# 16_-SP1_TYPEC_PWR_IN.net
KiCad netlist of a schematic drawn in Altium Designer
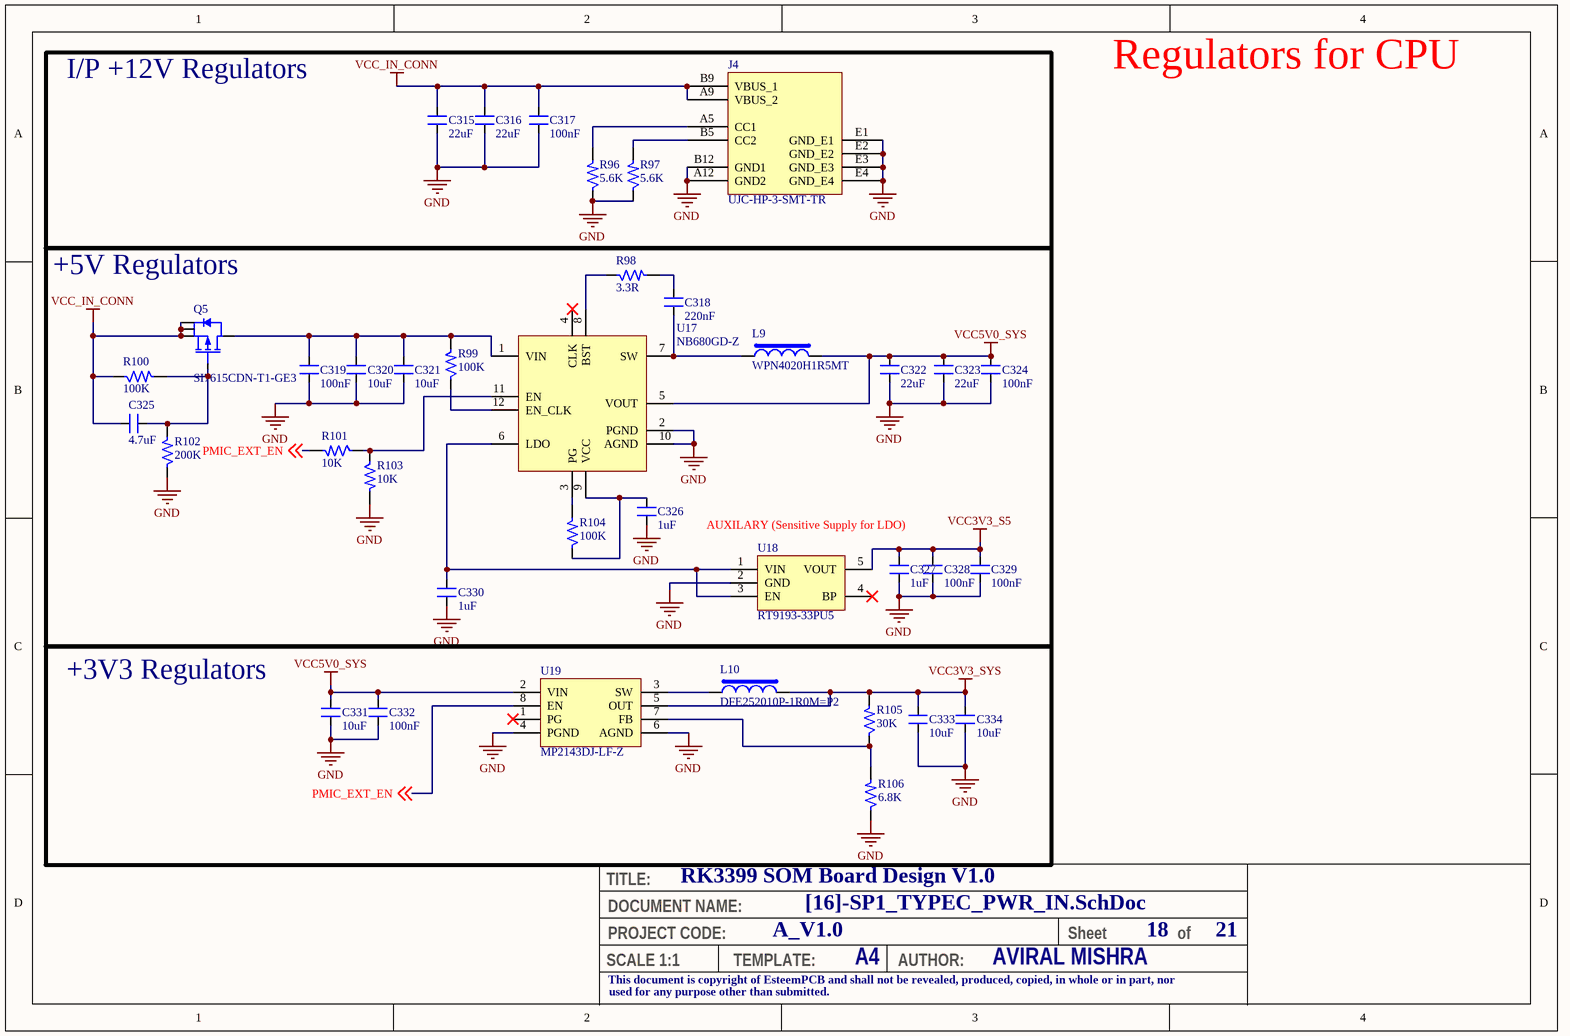
[diagram p0: [16]-SP1_TYPEC_PWR_IN.SchDoc]

(export (version "E")
  (design (tool "Eeschema 10.0.6"))
  (components
    (comp (ref "C315")
      (value "22uF")
      (footprint "CAP_0603")
      (description "22µF ±20% 10V Ceramic Capacitor X5R 0603 (1608 Metric)")
      (fields
        (field (name "MANUFACTURER") "Murata Electronics")
        (field (name "MANUFACTURER PART NUMBER") "GRM188R61A226ME15D")
      )
      (libsource (lib "RK3399 _Module_Schlib") (part "CAP_22uF-10V-20%-0603"))
    )
    (comp (ref "C316")
      (value "22uF")
      (footprint "CAP_0603")
      (description "22µF ±20% 10V Ceramic Capacitor X5R 0603 (1608 Metric)")
      (fields
        (field (name "MANUFACTURER") "Murata Electronics")
        (field (name "MANUFACTURER PART NUMBER") "GRM188R61A226ME15D")
      )
      (libsource (lib "RK3399 _Module_Schlib") (part "CAP_22uF-10V-20%-0603"))
    )
    (comp (ref "C317")
      (value "100nF")
      (footprint "CAP_0402")
      (description "0.1µF ±10% 25V Ceramic Capacitor X7R 0402 (1005 Metric)")
      (fields
        (field (name "MANUFACTURER") "Walsin Technology Corporation")
        (field (name "MANUFACTURER PART NUMBER") "0402B104K250CT")
      )
      (libsource (lib "RK3399 _Module_Schlib") (part "CAP_100nF-25V-10%-0402"))
    )
    (comp (ref "C318")
      (value "220nF")
      (footprint "CAP_0402")
      (description "0.22µF ±10% 10V Ceramic Capacitor X7R 0402 (1005 Metric)")
      (fields
        (field (name "MANUFACTURER") "Samsung Electro-Mechanics")
        (field (name "MANUFACTURER PART NUMBER") "CL05B224KP5NNNC")
      )
      (libsource (lib "RK3399 _Module_Schlib") (part "CAP_220nF-10V-10%-0402"))
    )
    (comp (ref "C319")
      (value "100nF")
      (footprint "CAP_0402")
      (description "0.1µF ±10% 25V Ceramic Capacitor X7R 0402 (1005 Metric)")
      (fields
        (field (name "MANUFACTURER") "Walsin Technology Corporation")
        (field (name "MANUFACTURER PART NUMBER") "0402B104K250CT")
      )
      (libsource (lib "RK3399 _Module_Schlib") (part "CAP_100nF-25V-10%-0402"))
    )
    (comp (ref "C320")
      (value "10uF")
      (footprint "CAP_0402")
      (description "10µF ±20% 10V Ceramic Capacitor X5R 0402 (1005 Metric)")
      (fields
        (field (name "MANUFACTURER PART NUMBER") "CL05A106MP5NUNC")
        (field (name "MANUFACTURER") "Samsung Electro-Mechanics")
      )
      (libsource (lib "RK3399 _Module_Schlib") (part "CAP_10uF-10V-20%-0402"))
    )
    (comp (ref "C321")
      (value "10uF")
      (footprint "CAP_0402")
      (description "10µF ±20% 10V Ceramic Capacitor X5R 0402 (1005 Metric)")
      (fields
        (field (name "MANUFACTURER PART NUMBER") "CL05A106MP5NUNC")
        (field (name "MANUFACTURER") "Samsung Electro-Mechanics")
      )
      (libsource (lib "RK3399 _Module_Schlib") (part "CAP_10uF-10V-20%-0402"))
    )
    (comp (ref "C322")
      (value "22uF")
      (footprint "CAP_0603")
      (description "22µF ±20% 10V Ceramic Capacitor X5R 0603 (1608 Metric)")
      (fields
        (field (name "MANUFACTURER") "Murata Electronics")
        (field (name "MANUFACTURER PART NUMBER") "GRM188R61A226ME15D")
      )
      (libsource (lib "RK3399 _Module_Schlib") (part "CAP_22uF-10V-20%-0603"))
    )
    (comp (ref "C323")
      (value "22uF")
      (footprint "CAP_0603")
      (description "22µF ±20% 10V Ceramic Capacitor X5R 0603 (1608 Metric)")
      (fields
        (field (name "MANUFACTURER") "Murata Electronics")
        (field (name "MANUFACTURER PART NUMBER") "GRM188R61A226ME15D")
      )
      (libsource (lib "RK3399 _Module_Schlib") (part "CAP_22uF-10V-20%-0603"))
    )
    (comp (ref "C324")
      (value "100nF")
      (footprint "CAP_0402")
      (description "0.1µF ±10% 25V Ceramic Capacitor X7R 0402 (1005 Metric)")
      (fields
        (field (name "MANUFACTURER") "Walsin Technology Corporation")
        (field (name "MANUFACTURER PART NUMBER") "0402B104K250CT")
      )
      (libsource (lib "RK3399 _Module_Schlib") (part "CAP_100nF-25V-10%-0402"))
    )
    (comp (ref "C325")
      (value "4.7uF")
      (footprint "CAP_0402")
      (description "4.7µF ±10% 10V Ceramic Capacitor X5R 0402 (1005 Metric)")
      (fields
        (field (name "MANUFACTURER") "Samsung Electro-Mechanics")
        (field (name "MANUFACTURER PART NUMBER") "CL05A475KP5NRNC")
      )
      (libsource (lib "RK3399 _Module_Schlib") (part "CAP_4.7uF-10V-10%-0402"))
    )
    (comp (ref "C326")
      (value "1uF")
      (footprint "CAP_0402")
      (description "1µF ±10% 16V Ceramic Capacitor X5R 0402 (1005 Metric)")
      (fields
        (field (name "MANUFACTURER") "Knowles Novacap")
        (field (name "MANUFACTURER PART NUMBER") "0402BW105K160YT")
      )
      (libsource (lib "RK3399 _Module_Schlib") (part "CAP_1uF-16V-10%-0402"))
    )
    (comp (ref "C327")
      (value "1uF")
      (footprint "CAP_0402")
      (description "1µF ±10% 16V Ceramic Capacitor X5R 0402 (1005 Metric)")
      (fields
        (field (name "MANUFACTURER") "Knowles Novacap")
        (field (name "MANUFACTURER PART NUMBER") "0402BW105K160YT")
      )
      (libsource (lib "RK3399 _Module_Schlib") (part "CAP_1uF-16V-10%-0402"))
    )
    (comp (ref "C328")
      (value "100nF")
      (footprint "CAP_0402")
      (description "0.1µF ±10% 25V Ceramic Capacitor X7R 0402 (1005 Metric)")
      (fields
        (field (name "MANUFACTURER") "Walsin Technology Corporation")
        (field (name "MANUFACTURER PART NUMBER") "0402B104K250CT")
      )
      (libsource (lib "RK3399 _Module_Schlib") (part "CAP_100nF-25V-10%-0402"))
    )
    (comp (ref "C329")
      (value "100nF")
      (footprint "CAP_0402")
      (description "0.1µF ±10% 25V Ceramic Capacitor X7R 0402 (1005 Metric)")
      (fields
        (field (name "MANUFACTURER") "Walsin Technology Corporation")
        (field (name "MANUFACTURER PART NUMBER") "0402B104K250CT")
      )
      (libsource (lib "RK3399 _Module_Schlib") (part "CAP_100nF-25V-10%-0402"))
    )
    (comp (ref "C330")
      (value "1uF")
      (footprint "CAP_0402")
      (description "1µF ±10% 16V Ceramic Capacitor X5R 0402 (1005 Metric)")
      (fields
        (field (name "MANUFACTURER") "Knowles Novacap")
        (field (name "MANUFACTURER PART NUMBER") "0402BW105K160YT")
      )
      (libsource (lib "RK3399 _Module_Schlib") (part "CAP_1uF-16V-10%-0402"))
    )
    (comp (ref "C331")
      (value "10uF")
      (footprint "CAP_0402")
      (description "10µF ±20% 10V Ceramic Capacitor X5R 0402 (1005 Metric)")
      (fields
        (field (name "MANUFACTURER PART NUMBER") "CL05A106MP5NUNC")
        (field (name "MANUFACTURER") "Samsung Electro-Mechanics")
      )
      (libsource (lib "RK3399 _Module_Schlib") (part "CAP_10uF-10V-20%-0402"))
    )
    (comp (ref "C332")
      (value "100nF")
      (footprint "CAP_0402")
      (description "0.1µF ±10% 25V Ceramic Capacitor X7R 0402 (1005 Metric)")
      (fields
        (field (name "MANUFACTURER") "Walsin Technology Corporation")
        (field (name "MANUFACTURER PART NUMBER") "0402B104K250CT")
      )
      (libsource (lib "RK3399 _Module_Schlib") (part "CAP_100nF-25V-10%-0402"))
    )
    (comp (ref "C333")
      (value "10uF")
      (footprint "CAP_0402")
      (description "10µF ±20% 10V Ceramic Capacitor X5R 0402 (1005 Metric)")
      (fields
        (field (name "MANUFACTURER PART NUMBER") "CL05A106MP5NUNC")
        (field (name "MANUFACTURER") "Samsung Electro-Mechanics")
      )
      (libsource (lib "RK3399 _Module_Schlib") (part "CAP_10uF-10V-20%-0402"))
    )
    (comp (ref "C334")
      (value "10uF")
      (footprint "CAP_0402")
      (description "10µF ±20% 10V Ceramic Capacitor X5R 0402 (1005 Metric)")
      (fields
        (field (name "MANUFACTURER PART NUMBER") "CL05A106MP5NUNC")
        (field (name "MANUFACTURER") "Samsung Electro-Mechanics")
      )
      (libsource (lib "RK3399 _Module_Schlib") (part "CAP_10uF-10V-20%-0402"))
    )
    (comp (ref "J4")
      (value "UJC-HP-3-SMT-TR")
      (footprint "CON6_48.4_UJC-HP-3-SMT-TR")
      (fields (field (name "MANUFACTURER") "CUI Devices"))
      (libsource (lib "RK3399 _Module_Schlib") (part "CON-TYPEC_6X1-100-RA-TH"))
    )
    (comp (ref "L9")
      (value "WPN4020H1R5MT")
      (footprint "IND_1616")
      (fields (field (name "MANUFACTURER") "Sunlord"))
      (libsource (lib "RK3399 _Module_Schlib") (part "IND_1.5uH-6A-20%-SMD"))
    )
    (comp (ref "L10")
      (value "DFE252010P-1R0M=P2")
      (footprint "IND_1008")
      (description "1µH Shielded Wirewound Inductor 3.8A 54mOhm Max 1008 (2520 Metric)")
      (fields (field (name "MANUFACTURER") "Murata Electronics"))
      (libsource (lib "RK3399 _Module_Schlib") (part "IND_1uH-3.8A-20%-1008"))
    )
    (comp (ref "Q5")
      (value "SI7615CDN-T1-GE3")
      (footprint "PowerPAK_1212-8_SMD")
      (description "P-Channel 20V 35A (Tc) 33W (Tc) Surface Mount PowerPAK® 1212-8")
      (fields (field (name "MANUFACTURER") "Vishay Siliconix"))
      (libsource (lib "RK3399 _Module_Schlib") (part "MOSFET-P_20V-35A-1212-8"))
    )
    (comp (ref "R96")
      (value "5.6K")
      (footprint "RES_0402")
      (fields
        (field (name "MANUFACTURER") "KOA Speer Electronics, Inc.")
        (field (name "MANUFACTURER PART NUMBER") "RK73H1ETTP5601F")
      )
      (libsource (lib "RK3399 _Module_Schlib") (part "RES_5.6K-0.1W-1%-0402"))
    )
    (comp (ref "R97")
      (value "5.6K")
      (footprint "RES_0402")
      (fields
        (field (name "MANUFACTURER") "KOA Speer Electronics, Inc.")
        (field (name "MANUFACTURER PART NUMBER") "RK73H1ETTP5601F")
      )
      (libsource (lib "RK3399 _Module_Schlib") (part "RES_5.6K-0.1W-1%-0402"))
    )
    (comp (ref "R98")
      (value "3.3R")
      (footprint "RES_0402")
      (fields
        (field (name "MANUFACTURER") "Panasonic Electronic Components")
        (field (name "MANUFACTURER PART NUMBER") "ERJ-U02F3R30X")
      )
      (libsource (lib "RK3399 _Module_Schlib") (part "RES_3.3R-0.1W-1%-0402"))
    )
    (comp (ref "R99")
      (value "100K")
      (footprint "RES_0402")
      (description "100 kOhms ±1% 0.1W, 1/10W Chip Resistor 0402 (1005 Metric) Anti-Sulfur Thin Film")
      (fields
        (field (name "MANUFACTURER") "Vishay Beyschlag/Draloric/BC Components")
        (field (name "MANUFACTURER PART NUMBER") "MCS04020C1003FE000")
      )
      (libsource (lib "RK3399 _Module_Schlib") (part "RES_100K-0.1W-1%-0402"))
    )
    (comp (ref "R100")
      (value "100K")
      (footprint "RES_0402")
      (description "100 kOhms ±1% 0.1W, 1/10W Chip Resistor 0402 (1005 Metric) Anti-Sulfur Thin Film")
      (fields
        (field (name "MANUFACTURER") "Vishay Beyschlag/Draloric/BC Components")
        (field (name "MANUFACTURER PART NUMBER") "MCS04020C1003FE000")
      )
      (libsource (lib "RK3399 _Module_Schlib") (part "RES_100K-0.1W-1%-0402"))
    )
    (comp (ref "R101")
      (value "10K")
      (footprint "RES_0402")
      (description "10 kOhms ±1% 0.1W, 1/10W Chip Resistor 0402 (1005 Metric) Anti-Sulfur Thin Film")
      (fields
        (field (name "MANUFACTURER") "Vishay Beyschlag/Draloric/BC Components")
        (field (name "MANUFACTURER PART NUMBER") "MCS04020C1002FE000")
      )
      (libsource (lib "RK3399 _Module_Schlib") (part "RES_10K-0.1W-1%-0402"))
    )
    (comp (ref "R102")
      (value "200K")
      (footprint "RES_0402")
      (description "200 kOhms ±1% 0.1W, 1/10W Chip Resistor 0402 (1005 Metric) Automotive AEC-Q200 Thick Film")
      (fields
        (field (name "MANUFACTURER") "Panasonic Electronic Components")
        (field (name "MANUFACTURER PART NUMBER") "ERJ-2RKF2003X")
      )
      (libsource (lib "RK3399 _Module_Schlib") (part "RES_200K-0.1W-1%-0402"))
    )
    (comp (ref "R103")
      (value "10K")
      (footprint "RES_0402")
      (description "10 kOhms ±1% 0.1W, 1/10W Chip Resistor 0402 (1005 Metric) Anti-Sulfur Thin Film")
      (fields
        (field (name "MANUFACTURER") "Vishay Beyschlag/Draloric/BC Components")
        (field (name "MANUFACTURER PART NUMBER") "MCS04020C1002FE000")
      )
      (libsource (lib "RK3399 _Module_Schlib") (part "RES_10K-0.1W-1%-0402"))
    )
    (comp (ref "R104")
      (value "100K")
      (footprint "RES_0402")
      (description "100 kOhms ±1% 0.1W, 1/10W Chip Resistor 0402 (1005 Metric) Anti-Sulfur Thin Film")
      (fields
        (field (name "MANUFACTURER") "Vishay Beyschlag/Draloric/BC Components")
        (field (name "MANUFACTURER PART NUMBER") "MCS04020C1003FE000")
      )
      (libsource (lib "RK3399 _Module_Schlib") (part "RES_100K-0.1W-1%-0402"))
    )
    (comp (ref "R105")
      (value "30K")
      (footprint "RES_0402")
      (fields
        (field (name "MANUFACTURER") "KOA Speer Electronics, Inc.")
        (field (name "MANUFACTURER PART NUMBER") "RK73H1ETTP3002F")
      )
      (libsource (lib "RK3399 _Module_Schlib") (part "RES_30K-0.1W-1%-0402"))
    )
    (comp (ref "R106")
      (value "6.8K")
      (footprint "RES_0402")
      (description "6.8 kOhms ±1% 0.1W, 1/10W Chip Resistor 0402 (1005 Metric) Anti-Sulfur Thin Film")
      (fields
        (field (name "MANUFACTURER PART NUMBER") "MCS04020C6801FE000")
        (field (name "MANUFACTURER") "Vishay Beyschlag/Draloric/BC Components")
      )
      (libsource (lib "RK3399 _Module_Schlib") (part "RES_6.8K-0.1W-1%-0402"))
    )
    (comp (ref "U17")
      (value "NB680GD-Z")
      (footprint "QFN-12_19_118X118_SMD")
      (description "Switching Voltage Regulators 26V Fixed 3.3 V-8A Sync Buck Converter")
      (fields (field (name "MANUFACTURER") "Monolithic Power Systems (MPS)"))
      (libsource (lib "RK3399 _Module_Schlib") (part "REG_3.3V-26V-8A-QFN-12"))
    )
    (comp (ref "U18")
      (value "RT9193-33PU5")
      (footprint "SC70-5")
      (description "SC-70-5 Dropout Regulators(LDO) RoHS")
      (fields (field (name "MANUFACTURER") "Richtek Tech"))
      (libsource (lib "RK3399 _Module_Schlib") (part "REG_3.3V-5.5V-300mA-SC-70-5"))
    )
    (comp (ref "U19")
      (value "MP2143DJ-LF-Z")
      (footprint "SOT23-8")
      (description "Switching Voltage Regulators 3A, 5.5V, 1.2MHz Sync Stp-Dwn Swtchr")
      (fields (field (name "MANUFACTURER") "Monolithic Power Systems (MPS)"))
      (libsource (lib "RK3399 _Module_Schlib") (part "REG_0.6~5V-5.5V-3A-TSOT-23-8"))
    )
  )
  (nets
    (net (code "1") (name "GND") (class "Default")
      (node (ref "C315") (pin "1") (pinfunction "1_1") (pintype "passive"))
      (node (ref "C316") (pin "1") (pinfunction "1_1") (pintype "passive"))
      (node (ref "C317") (pin "1") (pinfunction "1_1") (pintype "passive"))
      (node (ref "C319") (pin "1") (pinfunction "1_1") (pintype "passive"))
      (node (ref "C320") (pin "1") (pinfunction "1_1") (pintype "passive"))
      (node (ref "C321") (pin "1") (pinfunction "1_1") (pintype "passive"))
      (node (ref "C322") (pin "1") (pinfunction "1_1") (pintype "passive"))
      (node (ref "C323") (pin "1") (pinfunction "1_1") (pintype "passive"))
      (node (ref "C324") (pin "1") (pinfunction "1_1") (pintype "passive"))
      (node (ref "C326") (pin "1") (pinfunction "1_1") (pintype "passive"))
      (node (ref "C327") (pin "1") (pinfunction "1_1") (pintype "passive"))
      (node (ref "C328") (pin "1") (pinfunction "1_1") (pintype "passive"))
      (node (ref "C329") (pin "1") (pinfunction "1_1") (pintype "passive"))
      (node (ref "C330") (pin "1") (pinfunction "1_1") (pintype "passive"))
      (node (ref "C331") (pin "1") (pinfunction "1_1") (pintype "passive"))
      (node (ref "C332") (pin "1") (pinfunction "1_1") (pintype "passive"))
      (node (ref "C333") (pin "1") (pinfunction "1_1") (pintype "passive"))
      (node (ref "C334") (pin "1") (pinfunction "1_1") (pintype "passive"))
      (node (ref "J4") (pin "A12") (pinfunction "GND2_A12") (pintype "passive"))
      (node (ref "J4") (pin "B12") (pinfunction "GND1_B12") (pintype "passive"))
      (node (ref "J4") (pin "E1") (pinfunction "GND_E1_E1") (pintype "passive"))
      (node (ref "J4") (pin "E2") (pinfunction "GND_E2_E2") (pintype "passive"))
      (node (ref "J4") (pin "E3") (pinfunction "GND_E3_E3") (pintype "passive"))
      (node (ref "J4") (pin "E4") (pinfunction "GND_E4_E4") (pintype "passive"))
      (node (ref "R102") (pin "1") (pinfunction "1_1") (pintype "passive"))
      (node (ref "R103") (pin "2") (pinfunction "2_2") (pintype "passive"))
      (node (ref "R106") (pin "1") (pinfunction "1_1") (pintype "passive"))
      (node (ref "R96") (pin "1") (pinfunction "1_1") (pintype "passive"))
      (node (ref "R97") (pin "1") (pinfunction "1_1") (pintype "passive"))
      (node (ref "U17") (pin "10") (pinfunction "AGND_10") (pintype "passive"))
      (node (ref "U17") (pin "2") (pinfunction "PGND_2") (pintype "passive"))
      (node (ref "U18") (pin "2") (pinfunction "GND_2") (pintype "passive"))
      (node (ref "U19") (pin "4") (pinfunction "PGND_4") (pintype "passive"))
      (node (ref "U19") (pin "6") (pinfunction "AGND_6") (pintype "passive"))
    )
    (net (code "2") (name "Net-(C318-Pad2)") (class "Default")
      (node (ref "C318") (pin "2") (pinfunction "2_2") (pintype "passive"))
      (node (ref "R98") (pin "2") (pinfunction "2_2") (pintype "passive"))
    )
    (net (code "3") (name "Net-(J4-CC1)") (class "Default")
      (node (ref "J4") (pin "A5") (pinfunction "CC1_A5") (pintype "passive"))
      (node (ref "R96") (pin "2") (pinfunction "2_2") (pintype "passive"))
    )
    (net (code "4") (name "Net-(J4-CC2)") (class "Default")
      (node (ref "J4") (pin "B5") (pinfunction "CC2_B5") (pintype "passive"))
      (node (ref "R97") (pin "2") (pinfunction "2_2") (pintype "passive"))
    )
    (net (code "5") (name "Net-(Q5-D)") (class "Default")
      (node (ref "C319") (pin "2") (pinfunction "2_2") (pintype "passive"))
      (node (ref "C320") (pin "2") (pinfunction "2_2") (pintype "passive"))
      (node (ref "C321") (pin "2") (pinfunction "2_2") (pintype "passive"))
      (node (ref "Q5") (pin "5") (pinfunction "D_5") (pintype "passive"))
      (node (ref "R99") (pin "2") (pinfunction "2_2") (pintype "passive"))
      (node (ref "U17") (pin "1") (pinfunction "VIN_1") (pintype "passive"))
    )
    (net (code "6") (name "Net-(Q5-G)") (class "Default")
      (node (ref "C325") (pin "2") (pinfunction "2_2") (pintype "passive"))
      (node (ref "Q5") (pin "4") (pinfunction "G_4") (pintype "passive"))
      (node (ref "R100") (pin "2") (pinfunction "2_2") (pintype "passive"))
      (node (ref "R102") (pin "2") (pinfunction "2_2") (pintype "passive"))
    )
    (net (code "7") (name "Net-(U17-BST)") (class "Default")
      (node (ref "R98") (pin "1") (pinfunction "1_1") (pintype "passive"))
      (node (ref "U17") (pin "8") (pinfunction "BST_8") (pintype "passive"))
    )
    (net (code "8") (name "Net-(U17-EN)") (class "Default")
      (node (ref "R101") (pin "1") (pinfunction "1_1") (pintype "passive"))
      (node (ref "R103") (pin "1") (pinfunction "1_1") (pintype "passive"))
      (node (ref "U17") (pin "11") (pinfunction "EN_11") (pintype "passive"))
    )
    (net (code "9") (name "Net-(U17-EN_CLK)") (class "Default")
      (node (ref "R99") (pin "1") (pinfunction "1_1") (pintype "passive"))
      (node (ref "U17") (pin "12") (pinfunction "EN_CLK_12") (pintype "passive"))
    )
    (net (code "10") (name "Net-(U17-LDO)") (class "Default")
      (node (ref "C330") (pin "2") (pinfunction "2_2") (pintype "passive"))
      (node (ref "U17") (pin "6") (pinfunction "LDO_6") (pintype "passive"))
      (node (ref "U18") (pin "1") (pinfunction "VIN_1") (pintype "passive"))
      (node (ref "U18") (pin "3") (pinfunction "EN_3") (pintype "passive"))
    )
    (net (code "11") (name "Net-(U17-PG)") (class "Default")
      (node (ref "R104") (pin "2") (pinfunction "2_2") (pintype "passive"))
      (node (ref "U17") (pin "3") (pinfunction "PG_3") (pintype "passive"))
    )
    (net (code "12") (name "Net-(U17-SW)") (class "Default")
      (node (ref "C318") (pin "1") (pinfunction "1_1") (pintype "passive"))
      (node (ref "L9") (pin "1") (pinfunction "1_1") (pintype "passive"))
      (node (ref "U17") (pin "7") (pinfunction "SW_7") (pintype "passive"))
    )
    (net (code "13") (name "Net-(U17-VCC)") (class "Default")
      (node (ref "C326") (pin "2") (pinfunction "2_2") (pintype "passive"))
      (node (ref "R104") (pin "1") (pinfunction "1_1") (pintype "passive"))
      (node (ref "U17") (pin "9") (pinfunction "VCC_9") (pintype "passive"))
    )
    (net (code "14") (name "Net-(U19-FB)") (class "Default")
      (node (ref "R105") (pin "1") (pinfunction "1_1") (pintype "passive"))
      (node (ref "R106") (pin "2") (pinfunction "2_2") (pintype "passive"))
      (node (ref "U19") (pin "7") (pinfunction "FB_7") (pintype "passive"))
    )
    (net (code "15") (name "Net-(U19-SW)") (class "Default")
      (node (ref "L10") (pin "1") (pinfunction "1_1") (pintype "passive"))
      (node (ref "U19") (pin "3") (pinfunction "SW_3") (pintype "passive"))
    )
    (net (code "16") (name "PMIC_EXT_EN") (class "Default")
      (node (ref "R101") (pin "2") (pinfunction "2_2") (pintype "passive"))
      (node (ref "U19") (pin "8") (pinfunction "EN_8") (pintype "passive"))
    )
    (net (code "17") (name "VCC3V3_S5") (class "Default")
      (node (ref "C327") (pin "2") (pinfunction "2_2") (pintype "passive"))
      (node (ref "C328") (pin "2") (pinfunction "2_2") (pintype "passive"))
      (node (ref "C329") (pin "2") (pinfunction "2_2") (pintype "passive"))
      (node (ref "U18") (pin "5") (pinfunction "VOUT_5") (pintype "passive"))
    )
    (net (code "18") (name "VCC3V3_SYS") (class "Default")
      (node (ref "C333") (pin "2") (pinfunction "2_2") (pintype "passive"))
      (node (ref "C334") (pin "2") (pinfunction "2_2") (pintype "passive"))
      (node (ref "L10") (pin "2") (pinfunction "2_2") (pintype "passive"))
      (node (ref "R105") (pin "2") (pinfunction "2_2") (pintype "passive"))
      (node (ref "U19") (pin "5") (pinfunction "OUT_5") (pintype "passive"))
    )
    (net (code "19") (name "VCC5V0_SYS") (class "Default")
      (node (ref "C322") (pin "2") (pinfunction "2_2") (pintype "passive"))
      (node (ref "C323") (pin "2") (pinfunction "2_2") (pintype "passive"))
      (node (ref "C324") (pin "2") (pinfunction "2_2") (pintype "passive"))
      (node (ref "C331") (pin "2") (pinfunction "2_2") (pintype "passive"))
      (node (ref "C332") (pin "2") (pinfunction "2_2") (pintype "passive"))
      (node (ref "L9") (pin "2") (pinfunction "2_2") (pintype "passive"))
      (node (ref "U17") (pin "5") (pinfunction "VOUT_5") (pintype "passive"))
      (node (ref "U19") (pin "2") (pinfunction "VIN_2") (pintype "passive"))
    )
    (net (code "20") (name "VCC_IN_CONN") (class "Default")
      (node (ref "C315") (pin "2") (pinfunction "2_2") (pintype "passive"))
      (node (ref "C316") (pin "2") (pinfunction "2_2") (pintype "passive"))
      (node (ref "C317") (pin "2") (pinfunction "2_2") (pintype "passive"))
      (node (ref "C325") (pin "1") (pinfunction "1_1") (pintype "passive"))
      (node (ref "J4") (pin "A9") (pinfunction "VBUS_2_A9") (pintype "passive"))
      (node (ref "J4") (pin "B9") (pinfunction "VBUS_1_B9") (pintype "passive"))
      (node (ref "Q5") (pin "1") (pinfunction "S_1") (pintype "passive"))
      (node (ref "Q5") (pin "2") (pinfunction "S_2") (pintype "passive"))
      (node (ref "Q5") (pin "3") (pinfunction "S_3") (pintype "passive"))
      (node (ref "R100") (pin "1") (pinfunction "1_1") (pintype "passive"))
    )
    (net (code "21") (name "unconnected-(U17-CLK-Pad4)") (class "Default")
      (node (ref "U17") (pin "4") (pinfunction "CLK_4") (pintype "passive+no_connect"))
    )
    (net (code "22") (name "unconnected-(U18-BP-Pad4)") (class "Default")
      (node (ref "U18") (pin "4") (pinfunction "BP_4") (pintype "passive+no_connect"))
    )
    (net (code "23") (name "unconnected-(U19-PG-Pad1)") (class "Default")
      (node (ref "U19") (pin "1") (pinfunction "PG_1") (pintype "passive+no_connect"))
    )
  )
)
